# Bypass_FPGA_2V5.net
KiCad netlist of a schematic drawn in Altium Designer
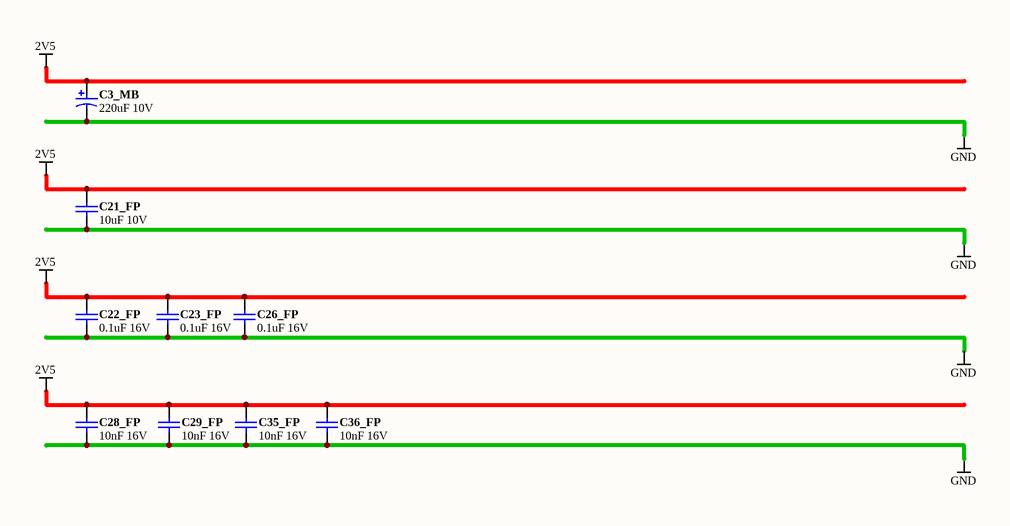
[diagram p0: Bypass_FPGA_2V5.SCHDOC]

(export (version "E")
  (design (tool "Eeschema 10.0.6"))
  (components
    (comp (ref "C3_MB")
      (value "220uF 10V")
      (footprint "CAPC7343-STAR")
      (description "Capacitor, Tantalum, 220uF 10% 10V MCCT-D (7343-31)")
      (fields (field (name "TOLERANCE") "10 %"))
      (libsource (lib "AltiumDesignLibrary") (part "CAP-P"))
    )
    (comp (ref "C21_FP")
      (value "10uF 10V")
      (footprint "CAPC2012-STAR")
      (description "Capacitor, Ceramic, 10uF 10% 10V 0805 (2012) X5R")
      (fields (field (name "TOLERANCE") "10 %"))
      (libsource (lib "AltiumDesignLibrary") (part "CAP-NP"))
    )
    (comp (ref "C22_FP")
      (value "0.1uF 16V")
      (footprint "CAPC1005-STAR")
      (description "Capacitor, Ceramic, 0.1uF 10% 16V 0402 (1005) X7R")
      (fields (field (name "TOLERANCE") "10 %"))
      (libsource (lib "AltiumDesignLibrary") (part "CAP-NP"))
    )
    (comp (ref "C23_FP")
      (value "0.1uF 16V")
      (footprint "CAPC1005-STAR")
      (description "Capacitor, Ceramic, 0.1uF 10% 16V 0402 (1005) X7R")
      (fields (field (name "TOLERANCE") "10 %"))
      (libsource (lib "AltiumDesignLibrary") (part "CAP-NP"))
    )
    (comp (ref "C26_FP")
      (value "0.1uF 16V")
      (footprint "CAPC1005-STAR")
      (description "Capacitor, Ceramic, 0.1uF 10% 16V 0402 (1005) X7R")
      (fields (field (name "TOLERANCE") "10 %"))
      (libsource (lib "AltiumDesignLibrary") (part "CAP-NP"))
    )
    (comp (ref "C28_FP")
      (value "10nF 16V")
      (footprint "CAPC1005-STAR")
      (description "Capacitor, Ceramic, 10nF 10% 16V 0402 (1005) X7R")
      (fields (field (name "TOLERANCE") "10 %"))
      (libsource (lib "AltiumDesignLibrary") (part "CAP-NP"))
    )
    (comp (ref "C29_FP")
      (value "10nF 16V")
      (footprint "CAPC1005-STAR")
      (description "Capacitor, Ceramic, 10nF 10% 16V 0402 (1005) X7R")
      (fields (field (name "TOLERANCE") "10 %"))
      (libsource (lib "AltiumDesignLibrary") (part "CAP-NP"))
    )
    (comp (ref "C35_FP")
      (value "10nF 16V")
      (footprint "CAPC1005-STAR")
      (description "Capacitor, Ceramic, 10nF 10% 16V 0402 (1005) X7R")
      (fields (field (name "TOLERANCE") "10 %"))
      (libsource (lib "AltiumDesignLibrary") (part "CAP-NP"))
    )
    (comp (ref "C36_FP")
      (value "10nF 16V")
      (footprint "CAPC1005-STAR")
      (description "Capacitor, Ceramic, 10nF 10% 16V 0402 (1005) X7R")
      (fields (field (name "TOLERANCE") "10 %"))
      (libsource (lib "AltiumDesignLibrary") (part "CAP-NP"))
    )
  )
  (nets
    (net (code "1") (name "2V5") (class "Default")
      (node (ref "C21_FP") (pin "1") (pinfunction "1_1") (pintype "passive"))
      (node (ref "C22_FP") (pin "1") (pinfunction "1_1") (pintype "passive"))
      (node (ref "C23_FP") (pin "1") (pinfunction "1_1") (pintype "passive"))
      (node (ref "C26_FP") (pin "1") (pinfunction "1_1") (pintype "passive"))
      (node (ref "C28_FP") (pin "1") (pinfunction "1_1") (pintype "passive"))
      (node (ref "C29_FP") (pin "1") (pinfunction "1_1") (pintype "passive"))
      (node (ref "C35_FP") (pin "1") (pinfunction "1_1") (pintype "passive"))
      (node (ref "C36_FP") (pin "1") (pinfunction "1_1") (pintype "passive"))
      (node (ref "C3_MB") (pin "1") (pinfunction "1_1") (pintype "passive"))
    )
    (net (code "2") (name "GND") (class "Default")
      (node (ref "C21_FP") (pin "2") (pinfunction "2_2") (pintype "passive"))
      (node (ref "C22_FP") (pin "2") (pinfunction "2_2") (pintype "passive"))
      (node (ref "C23_FP") (pin "2") (pinfunction "2_2") (pintype "passive"))
      (node (ref "C26_FP") (pin "2") (pinfunction "2_2") (pintype "passive"))
      (node (ref "C28_FP") (pin "2") (pinfunction "2_2") (pintype "passive"))
      (node (ref "C29_FP") (pin "2") (pinfunction "2_2") (pintype "passive"))
      (node (ref "C35_FP") (pin "2") (pinfunction "2_2") (pintype "passive"))
      (node (ref "C36_FP") (pin "2") (pinfunction "2_2") (pintype "passive"))
      (node (ref "C3_MB") (pin "2") (pinfunction "2_2") (pintype "passive"))
    )
  )
)
